# Input_Output.net
KiCad netlist of a schematic drawn in Altium Designer
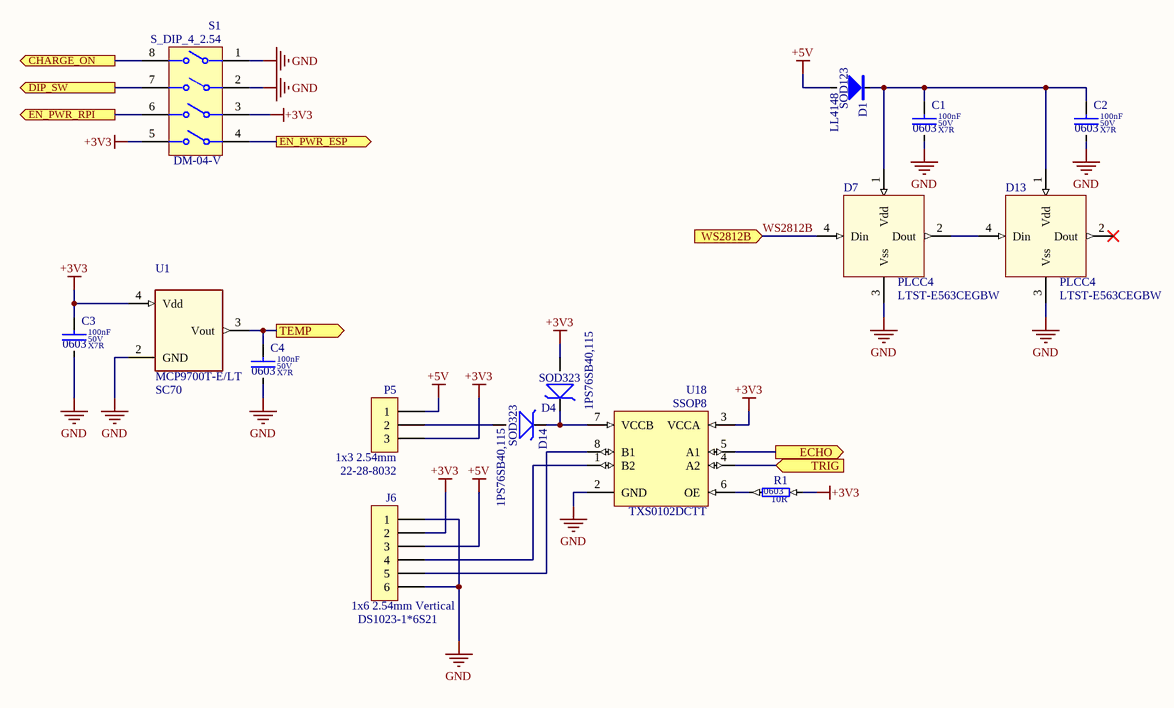
[diagram p0: Input_Output.SchDoc]

(export (version "E")
  (design (tool "Eeschema 10.0.6"))
  (components
    (comp (ref "C1")
      (value "100nF")
      (footprint "C_0603_1608")
      (description "Capacitor")
      (fields
        (field (name "DIELECTRIC") "X7R")
        (field (name "VOLTAGE") "50V")
        (field (name "SCH_FOOTPRINT") "0603")
        (field (name "PART NUMBER") "C_100nF_50V_X7R_0603_5")
        (field (name "MANUFACTURER") "Samsung")
      )
      (libsource (lib "Library") (part "C"))
    )
    (comp (ref "C2")
      (value "100nF")
      (footprint "C_0603_1608")
      (description "Capacitor")
      (fields
        (field (name "DIELECTRIC") "X7R")
        (field (name "VOLTAGE") "50V")
        (field (name "SCH_FOOTPRINT") "0603")
        (field (name "PART NUMBER") "C_100nF_50V_X7R_0603_5")
        (field (name "MANUFACTURER") "Samsung")
      )
      (libsource (lib "Library") (part "C"))
    )
    (comp (ref "C3")
      (value "100nF")
      (footprint "C_0603_1608")
      (description "Capacitor")
      (fields
        (field (name "DIELECTRIC") "X7R")
        (field (name "VOLTAGE") "50V")
        (field (name "SCH_FOOTPRINT") "0603")
        (field (name "PART NUMBER") "C_100nF_50V_X7R_0603_5")
        (field (name "MANUFACTURER") "Samsung")
      )
      (libsource (lib "Library") (part "C"))
    )
    (comp (ref "C4")
      (value "100nF")
      (footprint "C_0603_1608")
      (description "Capacitor")
      (fields
        (field (name "DIELECTRIC") "X7R")
        (field (name "VOLTAGE") "50V")
        (field (name "SCH_FOOTPRINT") "0603")
        (field (name "PART NUMBER") "C_100nF_50V_X7R_0603_5")
        (field (name "MANUFACTURER") "Samsung")
      )
      (libsource (lib "Library") (part "C"))
    )
    (comp (ref "D1")
      (value "LL4148")
      (footprint "SOD123")
      (fields
        (field (name "SCH_FOOTPRINT") "SOD123")
        (field (name "PART NUMBER") "D_1N4148W_0A15_75V_SOD123")
        (field (name "VOLTAGE") "75V")
        (field (name "MANUFACTURER") "Fairchild Semiconductor")
      )
      (libsource (lib "Library") (part "D"))
    )
    (comp (ref "D4")
      (value "1PS76SB40,115")
      (footprint "SOD323")
      (fields
        (field (name "SCH_FOOTPRINT") "SOD323")
        (field (name "PART NUMBER") "DS_1PS76SB40_40V_SOD323")
        (field (name "VOLTAGE") "40V")
        (field (name "MANUFACTURER") "Nexperia")
      )
      (libsource (lib "Library") (part "DS"))
    )
    (comp (ref "D7")
      (value "LTST-E563CEGBW")
      (footprint "PLCC4_5050")
      (fields
        (field (name "SCH_FOOTPRINT") "PLCC4")
        (field (name "PART NUMBER") "OL_LTST-E563CEGBW")
        (field (name "MANUFACTURER") "Lite-On")
        (field (name "Comment") "SMD LED with built-in embedded IC")
      )
      (libsource (lib "Library") (part "OL_WS2812B"))
    )
    (comp (ref "D13")
      (value "LTST-E563CEGBW")
      (footprint "PLCC4_5050")
      (fields
        (field (name "SCH_FOOTPRINT") "PLCC4")
        (field (name "PART NUMBER") "OL_LTST-E563CEGBW")
        (field (name "MANUFACTURER") "Lite-On")
        (field (name "Comment") "SMD LED with built-in embedded IC")
      )
      (libsource (lib "Library") (part "OL_WS2812B"))
    )
    (comp (ref "D14")
      (value "1PS76SB40,115")
      (footprint "SOD323")
      (fields
        (field (name "SCH_FOOTPRINT") "SOD323")
        (field (name "PART NUMBER") "DS_1PS76SB40_40V_SOD323")
        (field (name "VOLTAGE") "40V")
        (field (name "MANUFACTURER") "Nexperia")
      )
      (libsource (lib "Library") (part "DS"))
    )
    (comp (ref "J6")
      (value "DS1023-1*6S21")
      (footprint "J_HEADER_1x6_2.54_VERTICAL")
      (description "Pin Header")
      (fields
        (field (name "SCH_FOOTPRINT") "1x6 2.54mm Vertical")
        (field (name "PART NUMBER") "J_HEADER_1x6_2.54_VERTICAL")
        (field (name "MANUFACTURER") "Connfly")
      )
      (libsource (lib "Library") (part "J_HEADER_1x6"))
    )
    (comp (ref "P5")
      (value "22-28-8032")
      (footprint "P_HEADER_1x3_2.54_ANGLE")
      (description "Pin Header")
      (fields
        (field (name "SCH_FOOTPRINT") "1x3 2.54mm")
        (field (name "PART NUMBER") "P_HEADER_1x3_2.54_ANGLE")
        (field (name "MANUFACTURER") "Molex")
      )
      (libsource (lib "Library") (part "P_HEADER_1x3"))
    )
    (comp (ref "R1")
      (value "10R")
      (footprint "R_0603_1608")
      (fields
        (field (name "SCH_FOOTPRINT") "0603")
        (field (name "PART NUMBER") "R_10R_0603_1")
        (field (name "VOLTAGE") "50V")
        (field (name "POWER") "100mW")
      )
      (libsource (lib "Library") (part "R"))
    )
    (comp (ref "S1")
      (value "DM-04-V")
      (footprint "DM-04-V")
      (fields
        (field (name "SCH_FOOTPRINT") "S_DIP_4_2.54")
        (field (name "PART NUMBER") "S_DM-04-V")
        (field (name "MANUFACTURER") "DIPTRONICS")
        (field (name "Comment") "DIP SWITCH 4 POS")
      )
      (libsource (lib "Library") (part "S_DIP_SWITCH_4"))
    )
    (comp (ref "U1")
      (value "MCP9700T-E/LT")
      (footprint "SC70-5_SOT353_TSSOP5")
      (fields
        (field (name "PART NUMBER") "U_MCP9700T-E/LT")
        (field (name "SCH_FOOTPRINT") "SC70")
        (field (name "MANUFACTURER") "Microchip")
      )
      (libsource (lib "Library") (part "U_MCP9700T-E_LT"))
    )
    (comp (ref "U18")
      (value "TXS0102DCTT")
      (footprint "SSOP8_3x3")
      (fields
        (field (name "SCH_FOOTPRINT") "SSOP8")
        (field (name "PART NUMBER") "U_TXS0102DCTT")
        (field (name "MANUFACTURER") "Texas Instruments")
      )
      (libsource (lib "Library") (part "U_TXS0102_DCT_DCU"))
    )
  )
  (nets
    (net (code "1") (name "+3V3") (class "Default")
      (node (ref "C3") (pin "1") (pinfunction "1_1") (pintype "passive"))
      (node (ref "D4") (pin "2") (pintype "passive"))
      (node (ref "J6") (pin "2") (pinfunction "2_2") (pintype "passive"))
      (node (ref "P5") (pin "3") (pinfunction "3_3") (pintype "passive"))
      (node (ref "R1") (pin "1") (pinfunction "1_1") (pintype "input"))
      (node (ref "S1") (pin "3") (pinfunction "3_3") (pintype "passive"))
      (node (ref "S1") (pin "5") (pinfunction "5_5") (pintype "passive"))
      (node (ref "U1") (pin "4") (pinfunction "Vdd_4") (pintype "input"))
      (node (ref "U18") (pin "3") (pinfunction "VCCA_3") (pintype "input"))
    )
    (net (code "2") (name "+5V") (class "Default")
      (node (ref "D1") (pin "2") (pintype "passive"))
      (node (ref "J6") (pin "3") (pinfunction "3_3") (pintype "passive"))
      (node (ref "P5") (pin "1") (pinfunction "1_1") (pintype "passive"))
    )
    (net (code "3") (name "/CHARGE_ON") (class "Default")
      (node (ref "S1") (pin "8") (pinfunction "8_8") (pintype "passive"))
    )
    (net (code "4") (name "/DIP_SW") (class "Default")
      (node (ref "S1") (pin "7") (pinfunction "7_7") (pintype "passive"))
    )
    (net (code "5") (name "/ECHO") (class "Default")
      (node (ref "U18") (pin "5") (pinfunction "A1_5") (pintype "bidirectional"))
    )
    (net (code "6") (name "/EN_PWR_ESP") (class "Default")
      (node (ref "S1") (pin "4") (pinfunction "4_4") (pintype "passive"))
    )
    (net (code "7") (name "/EN_PWR_RPI") (class "Default")
      (node (ref "S1") (pin "6") (pinfunction "6_6") (pintype "passive"))
    )
    (net (code "8") (name "/TEMP") (class "Default")
      (node (ref "C4") (pin "1") (pinfunction "1_1") (pintype "passive"))
      (node (ref "U1") (pin "3") (pinfunction "Vout_3") (pintype "output"))
    )
    (net (code "9") (name "/TRIG") (class "Default")
      (node (ref "U18") (pin "4") (pinfunction "A2_4") (pintype "bidirectional"))
    )
    (net (code "10") (name "/WS2812B") (class "Default")
      (node (ref "D7") (pin "4") (pinfunction "Din_4") (pintype "input"))
    )
    (net (code "11") (name "GND") (class "Default")
      (node (ref "C1") (pin "2") (pinfunction "2_2") (pintype "passive"))
      (node (ref "C2") (pin "2") (pinfunction "2_2") (pintype "passive"))
      (node (ref "C3") (pin "2") (pinfunction "2_2") (pintype "passive"))
      (node (ref "C4") (pin "2") (pinfunction "2_2") (pintype "passive"))
      (node (ref "D13") (pin "3") (pinfunction "Vss_3") (pintype "power_in"))
      (node (ref "D7") (pin "3") (pinfunction "Vss_3") (pintype "power_in"))
      (node (ref "J6") (pin "1") (pinfunction "1_1") (pintype "passive"))
      (node (ref "J6") (pin "6") (pinfunction "6_6") (pintype "passive"))
      (node (ref "S1") (pin "1") (pinfunction "1_1") (pintype "passive"))
      (node (ref "S1") (pin "2") (pinfunction "2_2") (pintype "passive"))
      (node (ref "U1") (pin "2") (pinfunction "GND_2") (pintype "power_in"))
      (node (ref "U18") (pin "2") (pinfunction "GND_2") (pintype "power_in"))
    )
    (net (code "12") (name "Net-(D13-Din)") (class "Default")
      (node (ref "D13") (pin "4") (pinfunction "Din_4") (pintype "input"))
      (node (ref "D7") (pin "2") (pinfunction "Dout_2") (pintype "output"))
    )
    (net (code "13") (name "Net-(D13-Vdd)") (class "Default")
      (node (ref "C1") (pin "1") (pinfunction "1_1") (pintype "passive"))
      (node (ref "C2") (pin "1") (pinfunction "1_1") (pintype "passive"))
      (node (ref "D1") (pin "1") (pintype "passive"))
      (node (ref "D13") (pin "1") (pinfunction "Vdd_1") (pintype "input"))
      (node (ref "D7") (pin "1") (pinfunction "Vdd_1") (pintype "input"))
    )
    (net (code "14") (name "Net-(D14-Pad2)") (class "Default")
      (node (ref "D14") (pin "2") (pintype "passive"))
      (node (ref "P5") (pin "2") (pinfunction "2_2") (pintype "passive"))
    )
    (net (code "15") (name "Net-(U18-B1)") (class "Default")
      (node (ref "J6") (pin "5") (pinfunction "5_5") (pintype "passive"))
      (node (ref "U18") (pin "8") (pinfunction "B1_8") (pintype "bidirectional"))
    )
    (net (code "16") (name "Net-(U18-B2)") (class "Default")
      (node (ref "J6") (pin "4") (pinfunction "4_4") (pintype "passive"))
      (node (ref "U18") (pin "1") (pinfunction "B2_1") (pintype "bidirectional"))
    )
    (net (code "17") (name "Net-(U18-OE)") (class "Default")
      (node (ref "R1") (pin "2") (pinfunction "2_2") (pintype "output"))
      (node (ref "U18") (pin "6") (pinfunction "OE_6") (pintype "input"))
    )
    (net (code "18") (name "Net-(U18-VCCB)") (class "Default")
      (node (ref "D14") (pin "1") (pintype "passive"))
      (node (ref "D4") (pin "1") (pintype "passive"))
      (node (ref "U18") (pin "7") (pinfunction "VCCB_7") (pintype "input"))
    )
    (net (code "19") (name "unconnected-(D13-Dout-Pad2)") (class "Default")
      (node (ref "D13") (pin "2") (pinfunction "Dout_2") (pintype "output+no_connect"))
    )
  )
)
